# counter.net
KiCad netlist of a schematic drawn in EAGLE
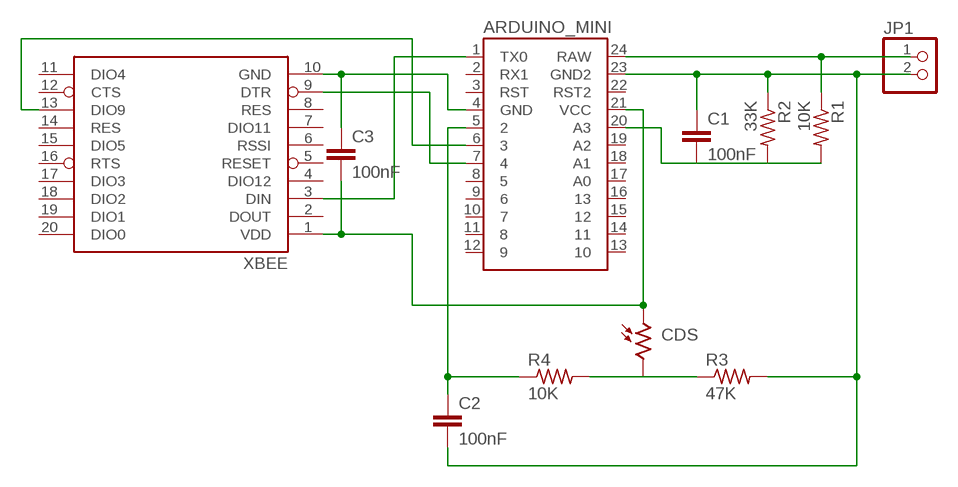
[diagram p0: schematic, sheet 1]

(export (version "E")
  (design (tool "Eeschema 10.0.6"))
  (components
    (comp (ref "ARDUINO_MINI")
      (value "ARDUINO_MINI")
      (footprint "eagle-import:ARDUINO_MINI")
      (libsource (lib "eagle-import") (part "ARDUINO_MINI"))
    )
    (comp (ref "C1")
      (value "100nF")
      (footprint "eagle-import:C050-024X044")
      (libsource (lib "eagle-import") (part "C-EU050-024X044"))
    )
    (comp (ref "C2")
      (value "100nF")
      (footprint "eagle-import:C050-024X044")
      (libsource (lib "eagle-import") (part "C-EU050-024X044"))
    )
    (comp (ref "C3")
      (value "100nF")
      (footprint "eagle-import:C050-024X044")
      (libsource (lib "eagle-import") (part "C-EU050-024X044"))
    )
    (comp (ref "CDS")
      (value "VT90N1")
      (footprint "eagle-import:VT900")
      (libsource (lib "eagle-import") (part "VT90N1"))
    )
    (comp (ref "JP1")
      (value "PINHD-1X2")
      (footprint "eagle-import:1X02")
      (libsource (lib "eagle-import") (part "PINHD-1X2"))
    )
    (comp (ref "R1")
      (value "10K")
      (footprint "eagle-import:0204_7")
      (libsource (lib "eagle-import") (part "R-US_0204/7"))
    )
    (comp (ref "R2")
      (value "33K")
      (footprint "eagle-import:0204_7")
      (libsource (lib "eagle-import") (part "R-US_0204/7"))
    )
    (comp (ref "R3")
      (value "47K")
      (footprint "eagle-import:0204_7")
      (libsource (lib "eagle-import") (part "R-US_0204/7"))
    )
    (comp (ref "R4")
      (value "10K")
      (footprint "eagle-import:0204_7")
      (libsource (lib "eagle-import") (part "R-US_0204/7"))
    )
    (comp (ref "XBEE")
      (value "XBEE-1B1")
      (footprint "eagle-import:XBEE-1")
      (libsource (lib "eagle-import") (part "XBEE-1B1"))
    )
  )
  (nets
    (net (code "1") (name "Net-(ARDUINO_MINI-2)") (class "Default")
      (node (ref "ARDUINO_MINI") (pin "5") (pinfunction "2_5") (pintype "bidirectional"))
      (node (ref "C2") (pin "1") (pinfunction "1_1") (pintype "passive"))
      (node (ref "R4") (pin "1") (pinfunction "1_1") (pintype "passive"))
    )
    (net (code "2") (name "Net-(ARDUINO_MINI-3)") (class "Default")
      (node (ref "ARDUINO_MINI") (pin "6") (pinfunction "3_6") (pintype "bidirectional"))
      (node (ref "XBEE") (pin "13") (pinfunction "DIO9_13") (pintype "bidirectional"))
    )
    (net (code "3") (name "Net-(ARDUINO_MINI-4)") (class "Default")
      (node (ref "ARDUINO_MINI") (pin "7") (pinfunction "4_7") (pintype "bidirectional"))
      (node (ref "XBEE") (pin "9") (pinfunction "DTR_9") (pintype "bidirectional"))
    )
    (net (code "4") (name "Net-(ARDUINO_MINI-A3)") (class "Default")
      (node (ref "ARDUINO_MINI") (pin "20") (pinfunction "A3_20") (pintype "bidirectional"))
      (node (ref "C1") (pin "2") (pinfunction "2_2") (pintype "passive"))
      (node (ref "R1") (pin "2") (pinfunction "2_2") (pintype "passive"))
      (node (ref "R2") (pin "2") (pinfunction "2_2") (pintype "passive"))
    )
    (net (code "5") (name "Net-(ARDUINO_MINI-GND)") (class "Default")
      (node (ref "ARDUINO_MINI") (pin "4") (pinfunction "GND_4") (pintype "bidirectional"))
      (node (ref "C3") (pin "1") (pinfunction "1_1") (pintype "passive"))
      (node (ref "XBEE") (pin "10") (pinfunction "GND_10") (pintype "power_in"))
    )
    (net (code "6") (name "Net-(ARDUINO_MINI-GND2)") (class "Default")
      (node (ref "ARDUINO_MINI") (pin "23") (pinfunction "GND2_23") (pintype "bidirectional"))
      (node (ref "C1") (pin "1") (pinfunction "1_1") (pintype "passive"))
      (node (ref "C2") (pin "2") (pinfunction "2_2") (pintype "passive"))
      (node (ref "JP1") (pin "2") (pinfunction "2_2") (pintype "passive"))
      (node (ref "R2") (pin "1") (pinfunction "1_1") (pintype "passive"))
      (node (ref "R3") (pin "2") (pinfunction "2_2") (pintype "passive"))
    )
    (net (code "7") (name "Net-(ARDUINO_MINI-RAW)") (class "Default")
      (node (ref "ARDUINO_MINI") (pin "24") (pinfunction "RAW_24") (pintype "bidirectional"))
      (node (ref "JP1") (pin "1") (pinfunction "1_1") (pintype "passive"))
      (node (ref "R1") (pin "1") (pinfunction "1_1") (pintype "passive"))
    )
    (net (code "8") (name "Net-(ARDUINO_MINI-TX0)") (class "Default")
      (node (ref "ARDUINO_MINI") (pin "1") (pinfunction "TX0_1") (pintype "bidirectional"))
      (node (ref "XBEE") (pin "3") (pinfunction "DIN_3") (pintype "input"))
    )
    (net (code "9") (name "Net-(ARDUINO_MINI-VCC)") (class "Default")
      (node (ref "ARDUINO_MINI") (pin "21") (pinfunction "VCC_21") (pintype "bidirectional"))
      (node (ref "C3") (pin "2") (pinfunction "2_2") (pintype "passive"))
      (node (ref "CDS") (pin "1") (pinfunction "1_1") (pintype "passive"))
      (node (ref "XBEE") (pin "1") (pinfunction "VDD_1") (pintype "power_in"))
    )
    (net (code "10") (name "Net-(CDS-Pad2)") (class "Default")
      (node (ref "CDS") (pin "2") (pinfunction "2_2") (pintype "passive"))
      (node (ref "R3") (pin "1") (pinfunction "1_1") (pintype "passive"))
      (node (ref "R4") (pin "2") (pinfunction "2_2") (pintype "passive"))
    )
    (net (code "11") (name "unconnected-(ARDUINO_MINI-5-Pad8)") (class "Default")
      (node (ref "ARDUINO_MINI") (pin "8") (pinfunction "5_8") (pintype "bidirectional"))
    )
    (net (code "12") (name "unconnected-(ARDUINO_MINI-6-Pad9)") (class "Default")
      (node (ref "ARDUINO_MINI") (pin "9") (pinfunction "6_9") (pintype "bidirectional"))
    )
    (net (code "13") (name "unconnected-(ARDUINO_MINI-7-Pad10)") (class "Default")
      (node (ref "ARDUINO_MINI") (pin "10") (pinfunction "7_10") (pintype "bidirectional"))
    )
    (net (code "14") (name "unconnected-(ARDUINO_MINI-8-Pad11)") (class "Default")
      (node (ref "ARDUINO_MINI") (pin "11") (pinfunction "8_11") (pintype "bidirectional"))
    )
    (net (code "15") (name "unconnected-(ARDUINO_MINI-9-Pad12)") (class "Default")
      (node (ref "ARDUINO_MINI") (pin "12") (pinfunction "9_12") (pintype "bidirectional"))
    )
    (net (code "16") (name "unconnected-(ARDUINO_MINI-10-Pad13)") (class "Default")
      (node (ref "ARDUINO_MINI") (pin "13") (pinfunction "10_13") (pintype "bidirectional"))
    )
    (net (code "17") (name "unconnected-(ARDUINO_MINI-11-Pad14)") (class "Default")
      (node (ref "ARDUINO_MINI") (pin "14") (pinfunction "11_14") (pintype "bidirectional"))
    )
    (net (code "18") (name "unconnected-(ARDUINO_MINI-12-Pad15)") (class "Default")
      (node (ref "ARDUINO_MINI") (pin "15") (pinfunction "12_15") (pintype "bidirectional"))
    )
    (net (code "19") (name "unconnected-(ARDUINO_MINI-13-Pad16)") (class "Default")
      (node (ref "ARDUINO_MINI") (pin "16") (pinfunction "13_16") (pintype "bidirectional"))
    )
    (net (code "20") (name "unconnected-(ARDUINO_MINI-A0-Pad17)") (class "Default")
      (node (ref "ARDUINO_MINI") (pin "17") (pinfunction "A0_17") (pintype "bidirectional"))
    )
    (net (code "21") (name "unconnected-(ARDUINO_MINI-A1-Pad18)") (class "Default")
      (node (ref "ARDUINO_MINI") (pin "18") (pinfunction "A1_18") (pintype "bidirectional"))
    )
    (net (code "22") (name "unconnected-(ARDUINO_MINI-A2-Pad19)") (class "Default")
      (node (ref "ARDUINO_MINI") (pin "19") (pinfunction "A2_19") (pintype "bidirectional"))
    )
    (net (code "23") (name "unconnected-(ARDUINO_MINI-RST-Pad3)") (class "Default")
      (node (ref "ARDUINO_MINI") (pin "3") (pinfunction "RST_3") (pintype "bidirectional"))
    )
    (net (code "24") (name "unconnected-(ARDUINO_MINI-RST2-Pad22)") (class "Default")
      (node (ref "ARDUINO_MINI") (pin "22") (pinfunction "RST2_22") (pintype "bidirectional"))
    )
    (net (code "25") (name "unconnected-(ARDUINO_MINI-RX1-Pad2)") (class "Default")
      (node (ref "ARDUINO_MINI") (pin "2") (pinfunction "RX1_2") (pintype "bidirectional"))
    )
    (net (code "26") (name "unconnected-(XBEE-CTS-Pad12)") (class "Default")
      (node (ref "XBEE") (pin "12") (pinfunction "CTS_12") (pintype "output"))
    )
    (net (code "27") (name "unconnected-(XBEE-DIO0-Pad20)") (class "Default")
      (node (ref "XBEE") (pin "20") (pinfunction "DIO0_20") (pintype "bidirectional"))
    )
    (net (code "28") (name "unconnected-(XBEE-DIO1-Pad19)") (class "Default")
      (node (ref "XBEE") (pin "19") (pinfunction "DIO1_19") (pintype "bidirectional"))
    )
    (net (code "29") (name "unconnected-(XBEE-DIO2-Pad18)") (class "Default")
      (node (ref "XBEE") (pin "18") (pinfunction "DIO2_18") (pintype "bidirectional"))
    )
    (net (code "30") (name "unconnected-(XBEE-DIO3-Pad17)") (class "Default")
      (node (ref "XBEE") (pin "17") (pinfunction "DIO3_17") (pintype "bidirectional"))
    )
    (net (code "31") (name "unconnected-(XBEE-DIO4-Pad11)") (class "Default")
      (node (ref "XBEE") (pin "11") (pinfunction "DIO4_11") (pintype "bidirectional"))
    )
    (net (code "32") (name "unconnected-(XBEE-DIO5-Pad15)") (class "Default")
      (node (ref "XBEE") (pin "15") (pinfunction "DIO5_15") (pintype "bidirectional"))
    )
    (net (code "33") (name "unconnected-(XBEE-DIO11-Pad7)") (class "Default")
      (node (ref "XBEE") (pin "7") (pinfunction "DIO11_7") (pintype "bidirectional"))
    )
    (net (code "34") (name "unconnected-(XBEE-DIO12-Pad4)") (class "Default")
      (node (ref "XBEE") (pin "4") (pinfunction "DIO12_4") (pintype "bidirectional"))
    )
    (net (code "35") (name "unconnected-(XBEE-DOUT-Pad2)") (class "Default")
      (node (ref "XBEE") (pin "2") (pinfunction "DOUT_2") (pintype "output"))
    )
    (net (code "36") (name "unconnected-(XBEE-RES-Pad8)") (class "Default")
      (node (ref "XBEE") (pin "8") (pinfunction "RES_8") (pintype "bidirectional"))
    )
    (net (code "37") (name "unconnected-(XBEE-RES-Pad14)") (class "Default")
      (node (ref "XBEE") (pin "14") (pinfunction "RES_14") (pintype "bidirectional"))
    )
    (net (code "38") (name "unconnected-(XBEE-RESET-Pad5)") (class "Default")
      (node (ref "XBEE") (pin "5") (pinfunction "RESET_5") (pintype "input"))
    )
    (net (code "39") (name "unconnected-(XBEE-RSSI-Pad6)") (class "Default")
      (node (ref "XBEE") (pin "6") (pinfunction "RSSI_6") (pintype "bidirectional"))
    )
    (net (code "40") (name "unconnected-(XBEE-RTS-Pad16)") (class "Default")
      (node (ref "XBEE") (pin "16") (pinfunction "RTS_16") (pintype "input"))
    )
  )
)
